# 100_top.net
KiCad netlist of a schematic drawn in Altium Designer
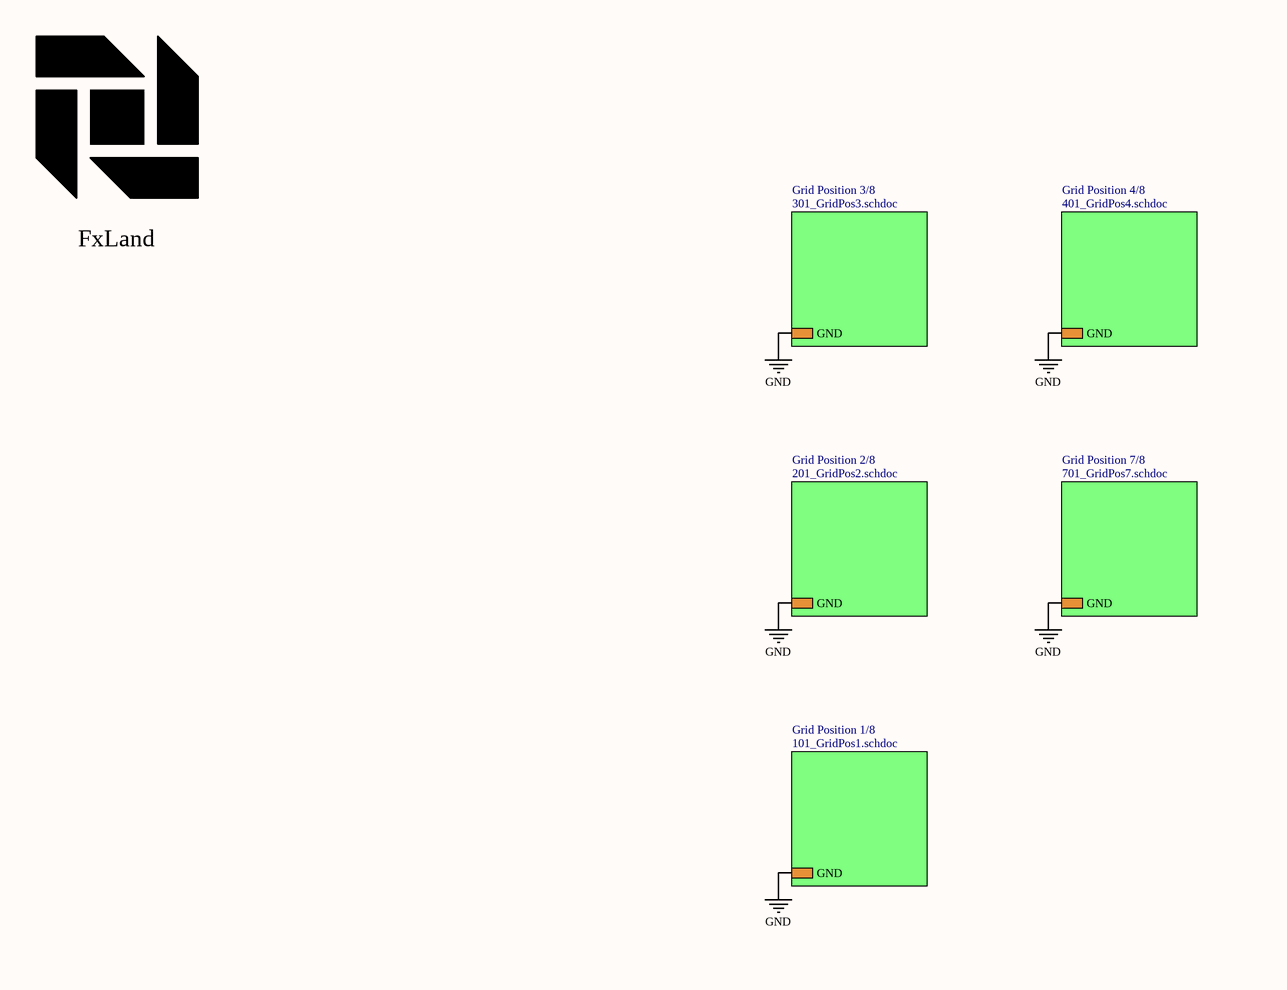
[diagram p0: 100_top.SchDoc, left]
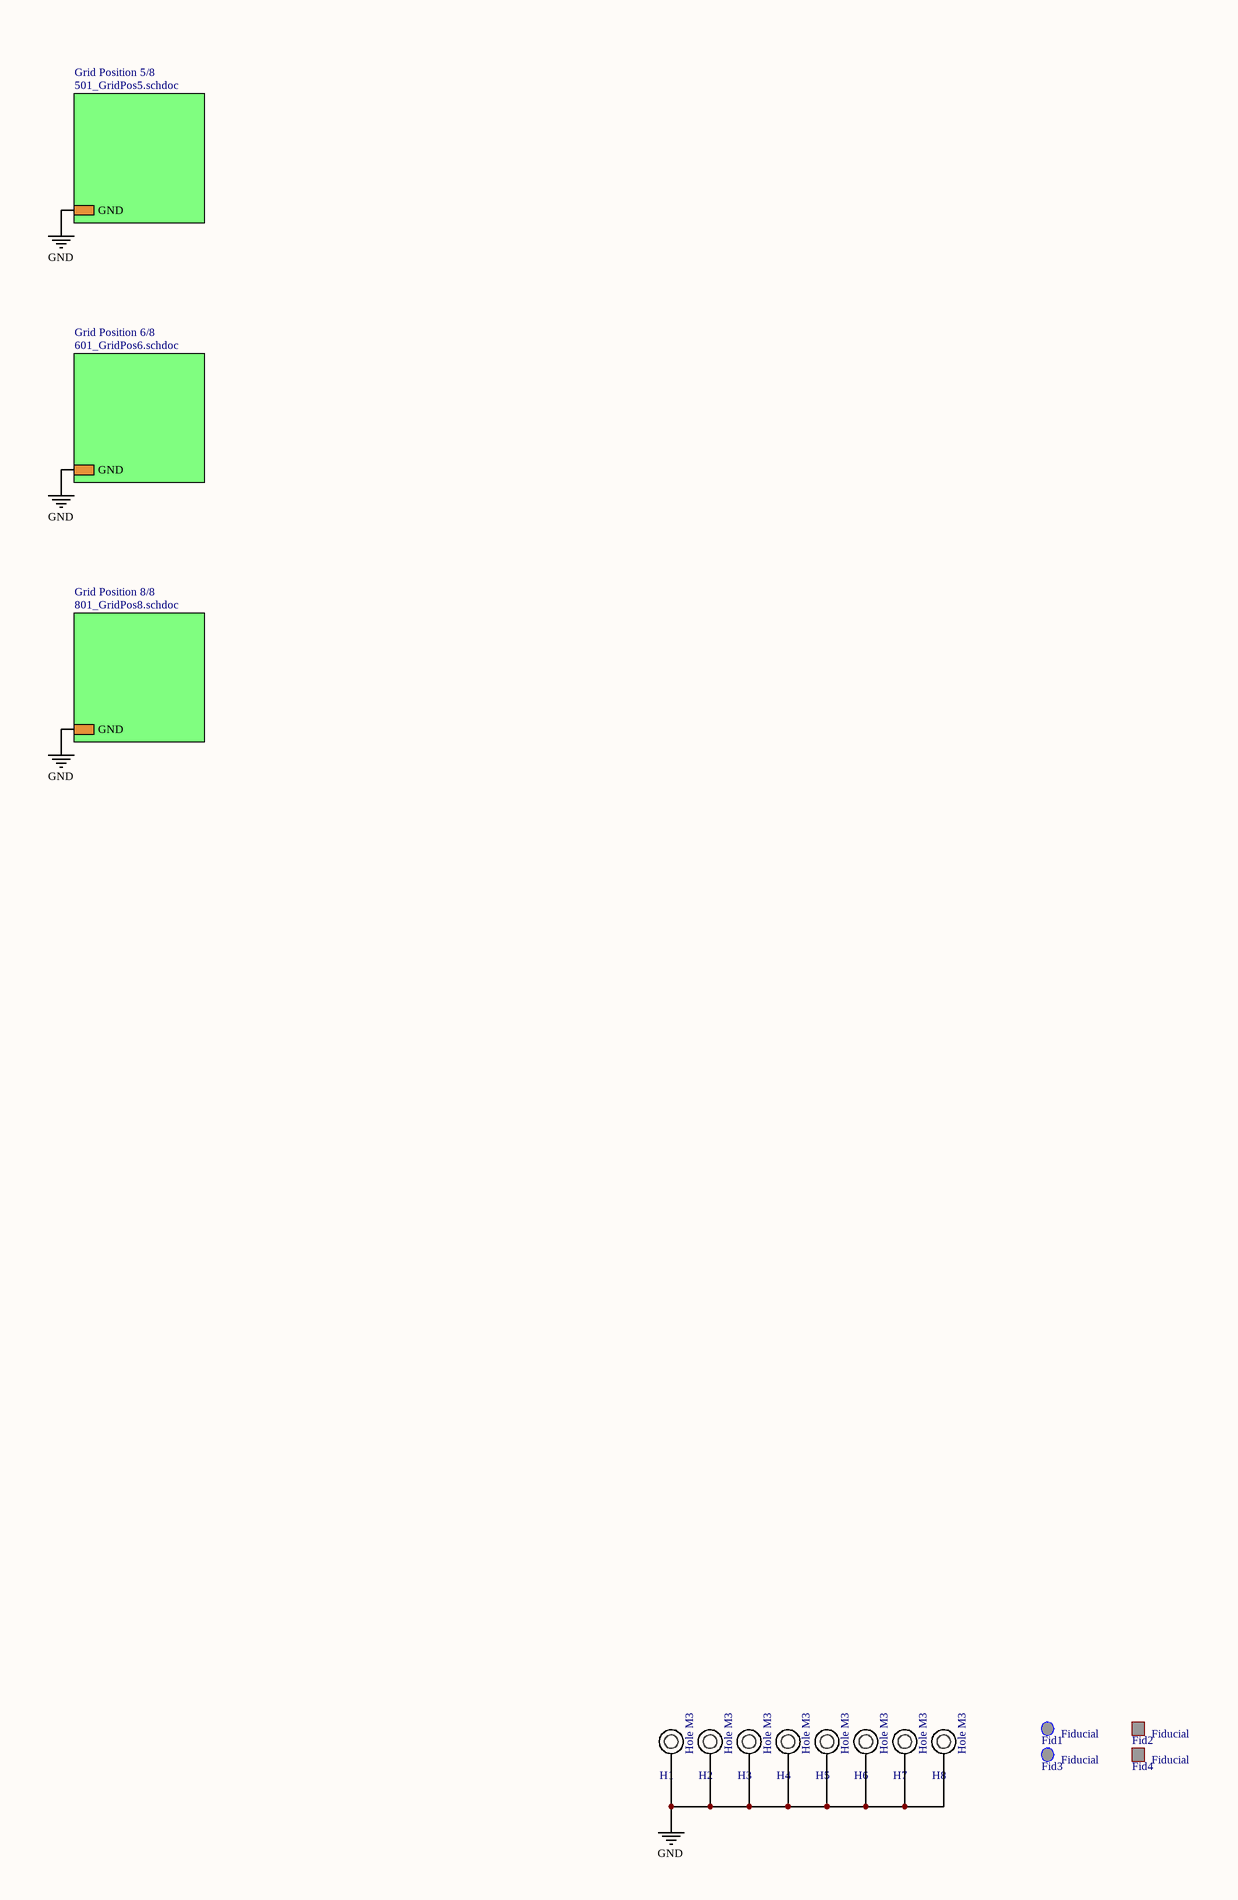
[diagram p1: 100_top.SchDoc, right]

(export (version "E")
  (design (tool "Eeschema 10.0.6"))
  (components
    (comp (ref "Fid1")
      (value "Fiducial")
      (footprint "FidR_1.0mm")
      (description "Fiducial Round 1mm")
      (fields (field (name "REFVAL") "Fiducial") (field (name "PART NUMBER") "ME0011"))
      (libsource (lib "GTS_Database") (part "FidR_1.0mm"))
    )
    (comp (ref "Fid2")
      (value "Fiducial")
      (footprint "FidS_1.0mm")
      (description "Fiducial Sqaure 1mm")
      (fields (field (name "REFVAL") "Fiducial") (field (name "PART NUMBER") "ME0012"))
      (libsource (lib "GTS_Database") (part "FidS_1.0mm"))
    )
    (comp (ref "Fid3")
      (value "Fiducial")
      (footprint "FidR_1.0mm")
      (description "Fiducial Round 1mm")
      (fields (field (name "REFVAL") "Fiducial") (field (name "PART NUMBER") "ME0011"))
      (libsource (lib "GTS_Database") (part "FidR_1.0mm"))
    )
    (comp (ref "Fid4")
      (value "Fiducial")
      (footprint "FidS_1.0mm")
      (description "Fiducial Sqaure 1mm")
      (fields (field (name "REFVAL") "Fiducial") (field (name "PART NUMBER") "ME0012"))
      (libsource (lib "GTS_Database") (part "FidS_1.0mm"))
    )
    (comp (ref "H1")
      (value "Hole M3")
      (footprint "HOLE_M3")
      (description "Mounting Hole M3")
      (fields (field (name "REFVAL") "Hole M3") (field (name "PART NUMBER") "ME0001"))
      (libsource (lib "GTS_Database") (part "HOLE"))
    )
    (comp (ref "H2")
      (value "Hole M3")
      (footprint "HOLE_M3")
      (description "Mounting Hole M3")
      (fields (field (name "REFVAL") "Hole M3") (field (name "PART NUMBER") "ME0001"))
      (libsource (lib "GTS_Database") (part "HOLE"))
    )
    (comp (ref "H3")
      (value "Hole M3")
      (footprint "HOLE_M3")
      (description "Mounting Hole M3")
      (fields (field (name "REFVAL") "Hole M3") (field (name "PART NUMBER") "ME0001"))
      (libsource (lib "GTS_Database") (part "HOLE"))
    )
    (comp (ref "H4")
      (value "Hole M3")
      (footprint "HOLE_M3")
      (description "Mounting Hole M3")
      (fields (field (name "REFVAL") "Hole M3") (field (name "PART NUMBER") "ME0001"))
      (libsource (lib "GTS_Database") (part "HOLE"))
    )
    (comp (ref "H5")
      (value "Hole M3")
      (footprint "HOLE_M3")
      (description "Mounting Hole M3")
      (fields (field (name "REFVAL") "Hole M3") (field (name "PART NUMBER") "ME0001"))
      (libsource (lib "GTS_Database") (part "HOLE"))
    )
    (comp (ref "H6")
      (value "Hole M3")
      (footprint "HOLE_M3")
      (description "Mounting Hole M3")
      (fields (field (name "REFVAL") "Hole M3") (field (name "PART NUMBER") "ME0001"))
      (libsource (lib "GTS_Database") (part "HOLE"))
    )
    (comp (ref "H7")
      (value "Hole M3")
      (footprint "HOLE_M3")
      (description "Mounting Hole M3")
      (fields (field (name "REFVAL") "Hole M3") (field (name "PART NUMBER") "ME0001"))
      (libsource (lib "GTS_Database") (part "HOLE"))
    )
    (comp (ref "H8")
      (value "Hole M3")
      (footprint "HOLE_M3")
      (description "Mounting Hole M3")
      (fields (field (name "REFVAL") "Hole M3") (field (name "PART NUMBER") "ME0001"))
      (libsource (lib "GTS_Database") (part "HOLE"))
    )
    (comp (ref "Logo FxLand1")
      (value "FxLand")
      (footprint "Logo_FxLand_3")
      (description "Logo FxLand 3")
      (fields (field (name "PART NUMBER") "ME0008"))
      (libsource (lib "GTS_Database") (part "Logo_FxLand_2"))
    )
  )
  (nets
    (net (code "1") (name "GND") (class "Default")
      (node (ref "H1") (pin "1") (pinfunction "1_1") (pintype "passive"))
      (node (ref "H2") (pin "1") (pinfunction "1_1") (pintype "passive"))
      (node (ref "H3") (pin "1") (pinfunction "1_1") (pintype "passive"))
      (node (ref "H4") (pin "1") (pinfunction "1_1") (pintype "passive"))
      (node (ref "H5") (pin "1") (pinfunction "1_1") (pintype "passive"))
      (node (ref "H6") (pin "1") (pinfunction "1_1") (pintype "passive"))
      (node (ref "H7") (pin "1") (pinfunction "1_1") (pintype "passive"))
      (node (ref "H8") (pin "1") (pinfunction "1_1") (pintype "passive"))
    )
  )
)
